# Emat_300v.net
KiCad netlist of a schematic drawn in EAGLE
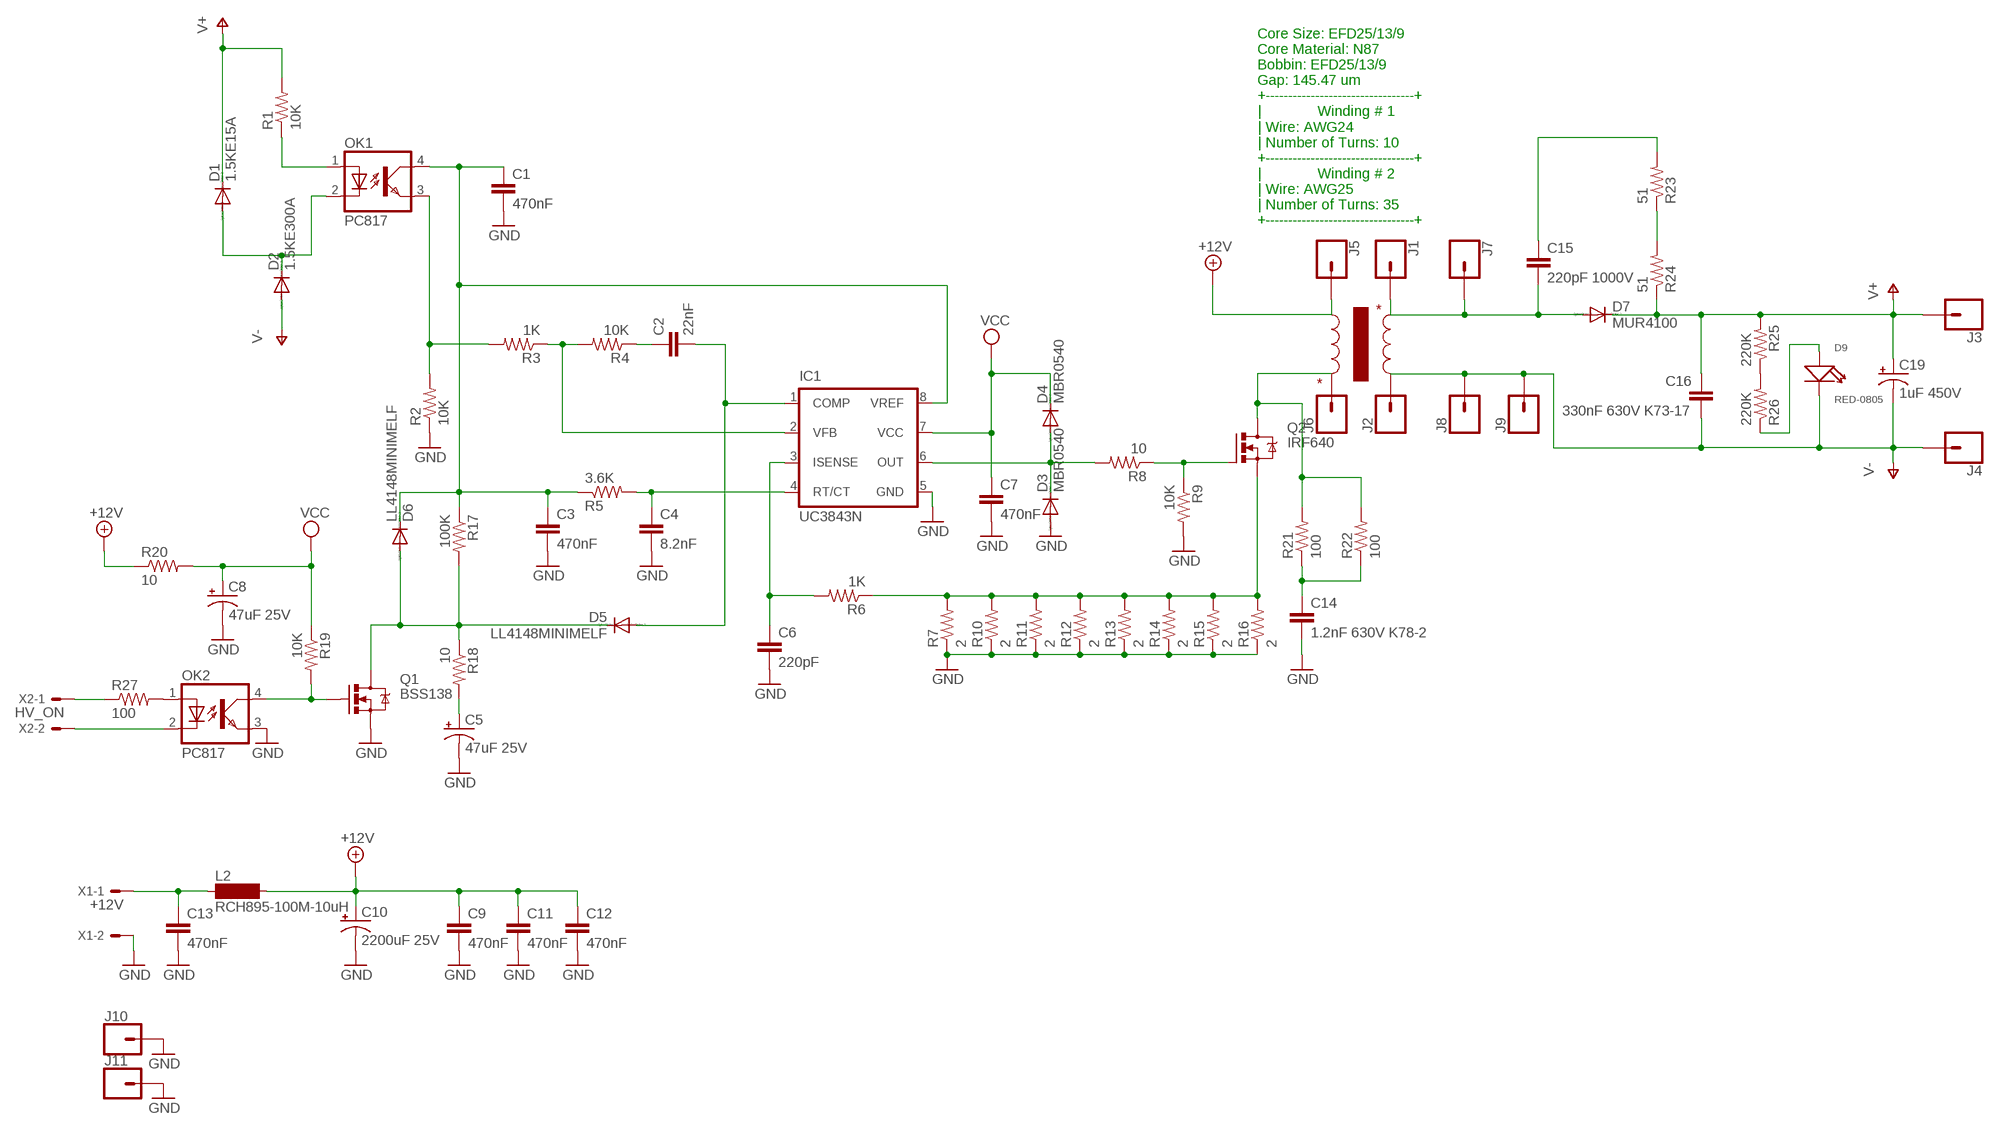
[diagram p0: schematic, sheet 1]

(export (version "E")
  (design (tool "Eeschema 10.0.6"))
  (components
    (comp (ref "C1")
      (value "470nF")
      (footprint "eagle-import:C0805")
      (libsource (lib "eagle-import") (part "C-EUC0805"))
    )
    (comp (ref "C2")
      (value "22nF")
      (footprint "eagle-import:C0805")
      (libsource (lib "eagle-import") (part "C-EUC0805"))
    )
    (comp (ref "C3")
      (value "470nF")
      (footprint "eagle-import:C0805")
      (libsource (lib "eagle-import") (part "C-EUC0805"))
    )
    (comp (ref "C4")
      (value "8.2nF")
      (footprint "eagle-import:C0805")
      (libsource (lib "eagle-import") (part "C-EUC0805"))
    )
    (comp (ref "C5")
      (value "47uF 25V")
      (footprint "eagle-import:E5-8,5")
      (libsource (lib "eagle-import") (part "CPOL-USE5-8.5"))
    )
    (comp (ref "C6")
      (value "220pF")
      (footprint "eagle-import:C0805")
      (libsource (lib "eagle-import") (part "C-EUC0805"))
    )
    (comp (ref "C7")
      (value "470nF")
      (footprint "eagle-import:C0805")
      (libsource (lib "eagle-import") (part "C-EUC0805"))
    )
    (comp (ref "C8")
      (value "47uF 25V")
      (footprint "eagle-import:E5-8,5")
      (libsource (lib "eagle-import") (part "CPOL-USE5-8.5"))
    )
    (comp (ref "C9")
      (value "470nF")
      (footprint "eagle-import:C0805")
      (libsource (lib "eagle-import") (part "C-EUC0805"))
    )
    (comp (ref "C10")
      (value "2200uF 25V")
      (footprint "eagle-import:E7,5-18")
      (libsource (lib "eagle-import") (part "CPOL-USE7.5-18"))
    )
    (comp (ref "C11")
      (value "470nF")
      (footprint "eagle-import:C0805")
      (libsource (lib "eagle-import") (part "C-EUC0805"))
    )
    (comp (ref "C12")
      (value "470nF")
      (footprint "eagle-import:C0805")
      (libsource (lib "eagle-import") (part "C-EUC0805"))
    )
    (comp (ref "C13")
      (value "470nF")
      (footprint "eagle-import:C0805")
      (libsource (lib "eagle-import") (part "C-EUC0805"))
    )
    (comp (ref "C14")
      (value "1.2nF 630V K78-2")
      (footprint "eagle-import:C150-064X183")
      (libsource (lib "eagle-import") (part "C-EU150-064X183"))
    )
    (comp (ref "C15")
      (value "220pF 1000V")
      (footprint "eagle-import:C075-042X103")
      (libsource (lib "eagle-import") (part "C-EU075-042X103"))
    )
    (comp (ref "C16")
      (value "330nF 630V K73-17")
      (footprint "eagle-import:C225-062X268")
      (libsource (lib "eagle-import") (part "C-EU225-062X268"))
    )
    (comp (ref "C19")
      (value "1uF 450V")
      (footprint "eagle-import:E5-8,5")
      (libsource (lib "eagle-import") (part "CPOL-USE5-8.5"))
    )
    (comp (ref "D1")
      (value "1.5KE15A")
      (footprint "eagle-import:DO201-15")
      (libsource (lib "eagle-import") (part "DIODE-DO201-15"))
    )
    (comp (ref "D2")
      (value "1.5KE300A")
      (footprint "eagle-import:DO201-15")
      (libsource (lib "eagle-import") (part "DIODE-DO201-15"))
    )
    (comp (ref "D3")
      (value "MBR0540")
      (footprint "eagle-import:SOD123")
      (libsource (lib "eagle-import") (part "DIODE-SOD123"))
    )
    (comp (ref "D4")
      (value "MBR0540")
      (footprint "eagle-import:SOD123")
      (libsource (lib "eagle-import") (part "DIODE-SOD123"))
    )
    (comp (ref "D5")
      (value "LL4148MINIMELF")
      (footprint "eagle-import:MINIMELF")
      (libsource (lib "eagle-import") (part "LL4148MINIMELF"))
    )
    (comp (ref "D6")
      (value "LL4148MINIMELF")
      (footprint "eagle-import:MINIMELF")
      (libsource (lib "eagle-import") (part "LL4148MINIMELF"))
    )
    (comp (ref "D7")
      (value "MUR4100")
      (footprint "eagle-import:DO201-15")
      (libsource (lib "eagle-import") (part "DIODE-DO201-15"))
    )
    (comp (ref "D9")
      (value "RED-0805")
      (footprint "eagle-import:LED-0805")
      (fields (field (name "MPN") "17-215SYGC/S530-E2/TR8"))
      (libsource (lib "eagle-import") (part "SMD-LED-CLEAR-GREEN(0805)"))
    )
    (comp (ref "IC1")
      (value "UC3843N")
      (footprint "eagle-import:DIL08")
      (libsource (lib "eagle-import") (part "UC384N3"))
    )
    (comp (ref "J1")
      (value "CONN_01PTH_NO_SILK_KIT")
      (footprint "eagle-import:1X01NS_KIT")
      (libsource (lib "eagle-import") (part "CONN_01PTH_NO_SILK_KIT"))
    )
    (comp (ref "J2")
      (value "CONN_01PTH_NO_SILK_KIT")
      (footprint "eagle-import:1X01NS_KIT")
      (libsource (lib "eagle-import") (part "CONN_01PTH_NO_SILK_KIT"))
    )
    (comp (ref "J3")
      (value "CONN_01PTH_NO_SILK_KIT")
      (footprint "eagle-import:1X01NS_KIT")
      (libsource (lib "eagle-import") (part "CONN_01PTH_NO_SILK_KIT"))
    )
    (comp (ref "J4")
      (value "CONN_01PTH_NO_SILK_KIT")
      (footprint "eagle-import:1X01NS_KIT")
      (libsource (lib "eagle-import") (part "CONN_01PTH_NO_SILK_KIT"))
    )
    (comp (ref "J5")
      (value "CONN_01PTH_NO_SILK_KIT")
      (footprint "eagle-import:1X01NS_KIT")
      (libsource (lib "eagle-import") (part "CONN_01PTH_NO_SILK_KIT"))
    )
    (comp (ref "J6")
      (value "CONN_01PTH_NO_SILK_KIT")
      (footprint "eagle-import:1X01NS_KIT")
      (libsource (lib "eagle-import") (part "CONN_01PTH_NO_SILK_KIT"))
    )
    (comp (ref "J7")
      (value "CONN_01PTH_NO_SILK_KIT")
      (footprint "eagle-import:1X01NS_KIT")
      (libsource (lib "eagle-import") (part "CONN_01PTH_NO_SILK_KIT"))
    )
    (comp (ref "J8")
      (value "CONN_01PTH_NO_SILK_KIT")
      (footprint "eagle-import:1X01NS_KIT")
      (libsource (lib "eagle-import") (part "CONN_01PTH_NO_SILK_KIT"))
    )
    (comp (ref "J9")
      (value "CONN_01PTH_NO_SILK_KIT")
      (footprint "eagle-import:1X01NS_KIT")
      (libsource (lib "eagle-import") (part "CONN_01PTH_NO_SILK_KIT"))
    )
    (comp (ref "J10")
      (value "CONN_01PTH_NO_SILK_KIT")
      (footprint "eagle-import:1X01NS_KIT")
      (libsource (lib "eagle-import") (part "CONN_01PTH_NO_SILK_KIT"))
    )
    (comp (ref "J11")
      (value "CONN_01PTH_NO_SILK_KIT")
      (footprint "eagle-import:1X01NS_KIT")
      (libsource (lib "eagle-import") (part "CONN_01PTH_NO_SILK_KIT"))
    )
    (comp (ref "L2")
      (value "RCH895-100M-10uH")
      (footprint "eagle-import:BS11")
      (libsource (lib "eagle-import") (part "RCH-89511"))
    )
    (comp (ref "OK1")
      (value "PC817")
      (footprint "eagle-import:DIL04")
      (fields (field (name "MPN") "PC817X4J000F"))
      (libsource (lib "eagle-import") (part "PC817"))
    )
    (comp (ref "OK2")
      (value "PC817")
      (footprint "eagle-import:DIL04")
      (fields (field (name "MPN") "PC817X4J000F"))
      (libsource (lib "eagle-import") (part "PC817"))
    )
    (comp (ref "Q1")
      (value "BSS138")
      (footprint "eagle-import:SOT23-3")
      (libsource (lib "eagle-import") (part "MOSFET-NCHANNELBSS138"))
    )
    (comp (ref "Q2")
      (value "IRF640")
      (footprint "eagle-import:TO220BV")
      (libsource (lib "eagle-import") (part "IRF640"))
    )
    (comp (ref "R1")
      (value "10K")
      (footprint "eagle-import:R1206")
      (libsource (lib "eagle-import") (part "R-US_R1206"))
    )
    (comp (ref "R2")
      (value "10K")
      (footprint "eagle-import:R1206")
      (libsource (lib "eagle-import") (part "R-US_R1206"))
    )
    (comp (ref "R3")
      (value "1K")
      (footprint "eagle-import:R1206")
      (libsource (lib "eagle-import") (part "R-US_R1206"))
    )
    (comp (ref "R4")
      (value "10K")
      (footprint "eagle-import:R1206")
      (libsource (lib "eagle-import") (part "R-US_R1206"))
    )
    (comp (ref "R5")
      (value "3.6K")
      (footprint "eagle-import:R1206")
      (libsource (lib "eagle-import") (part "R-US_R1206"))
    )
    (comp (ref "R6")
      (value "1K")
      (footprint "eagle-import:R1206")
      (libsource (lib "eagle-import") (part "R-US_R1206"))
    )
    (comp (ref "R7")
      (value "2")
      (footprint "eagle-import:R1206")
      (libsource (lib "eagle-import") (part "R-US_R1206"))
    )
    (comp (ref "R8")
      (value "10")
      (footprint "eagle-import:R1206")
      (libsource (lib "eagle-import") (part "R-US_R1206"))
    )
    (comp (ref "R9")
      (value "10K")
      (footprint "eagle-import:R1206")
      (libsource (lib "eagle-import") (part "R-US_R1206"))
    )
    (comp (ref "R10")
      (value "2")
      (footprint "eagle-import:R1206")
      (libsource (lib "eagle-import") (part "R-US_R1206"))
    )
    (comp (ref "R11")
      (value "2")
      (footprint "eagle-import:R1206")
      (libsource (lib "eagle-import") (part "R-US_R1206"))
    )
    (comp (ref "R12")
      (value "2")
      (footprint "eagle-import:R1206")
      (libsource (lib "eagle-import") (part "R-US_R1206"))
    )
    (comp (ref "R13")
      (value "2")
      (footprint "eagle-import:R1206")
      (libsource (lib "eagle-import") (part "R-US_R1206"))
    )
    (comp (ref "R14")
      (value "2")
      (footprint "eagle-import:R1206")
      (libsource (lib "eagle-import") (part "R-US_R1206"))
    )
    (comp (ref "R15")
      (value "2")
      (footprint "eagle-import:R1206")
      (libsource (lib "eagle-import") (part "R-US_R1206"))
    )
    (comp (ref "R16")
      (value "2")
      (footprint "eagle-import:R1206")
      (libsource (lib "eagle-import") (part "R-US_R1206"))
    )
    (comp (ref "R17")
      (value "100K")
      (footprint "eagle-import:R1206")
      (libsource (lib "eagle-import") (part "R-US_R1206"))
    )
    (comp (ref "R18")
      (value "10")
      (footprint "eagle-import:R1206")
      (libsource (lib "eagle-import") (part "R-US_R1206"))
    )
    (comp (ref "R19")
      (value "10K")
      (footprint "eagle-import:R1206")
      (libsource (lib "eagle-import") (part "R-US_R1206"))
    )
    (comp (ref "R20")
      (value "10")
      (footprint "eagle-import:R1206")
      (libsource (lib "eagle-import") (part "R-US_R1206"))
    )
    (comp (ref "R21")
      (value "100")
      (footprint "eagle-import:R2512")
      (libsource (lib "eagle-import") (part "R-US_R2512"))
    )
    (comp (ref "R22")
      (value "100")
      (footprint "eagle-import:R2512")
      (libsource (lib "eagle-import") (part "R-US_R2512"))
    )
    (comp (ref "R23")
      (value "51")
      (footprint "eagle-import:R1206")
      (libsource (lib "eagle-import") (part "R-US_R1206"))
    )
    (comp (ref "R24")
      (value "51")
      (footprint "eagle-import:R1206")
      (libsource (lib "eagle-import") (part "R-US_R1206"))
    )
    (comp (ref "R25")
      (value "220K")
      (footprint "eagle-import:R1206")
      (libsource (lib "eagle-import") (part "R-US_R1206"))
    )
    (comp (ref "R26")
      (value "220K")
      (footprint "eagle-import:R1206")
      (libsource (lib "eagle-import") (part "R-US_R1206"))
    )
    (comp (ref "R27")
      (value "100")
      (footprint "eagle-import:R1206")
      (libsource (lib "eagle-import") (part "R-US_R1206"))
    )
    (comp (ref "X1")
      (value "+12V")
      (footprint "eagle-import:22-23-2021")
      (fields (field (name "MF") "MOLEX") (field (name "MPN") "22-23-2021"))
      (libsource (lib "eagle-import") (part "22-23-2021"))
    )
    (comp (ref "X2")
      (value "HV_ON")
      (footprint "eagle-import:22-23-2021")
      (fields (field (name "MF") "MOLEX") (field (name "MPN") "22-23-2021"))
      (libsource (lib "eagle-import") (part "22-23-2021"))
    )
  )
  (nets
    (net (code "1") (name "+12V") (class "Default")
      (node (ref "C10") (pin "+") (pinfunction "+_+") (pintype "passive"))
      (node (ref "C11") (pin "1") (pinfunction "1_1") (pintype "passive"))
      (node (ref "C12") (pin "1") (pinfunction "1_1") (pintype "passive"))
      (node (ref "C9") (pin "1") (pinfunction "1_1") (pintype "passive"))
      (node (ref "J5") (pin "1") (pinfunction "1_1") (pintype "passive"))
      (node (ref "L2") (pin "2") (pinfunction "2_2") (pintype "passive"))
      (node (ref "R20") (pin "1") (pinfunction "1_1") (pintype "passive"))
    )
    (net (code "2") (name "GND") (class "Default")
      (node (ref "C1") (pin "2") (pinfunction "2_2") (pintype "passive"))
      (node (ref "C10") (pin "-") (pinfunction "-_-") (pintype "passive"))
      (node (ref "C11") (pin "2") (pinfunction "2_2") (pintype "passive"))
      (node (ref "C12") (pin "2") (pinfunction "2_2") (pintype "passive"))
      (node (ref "C13") (pin "2") (pinfunction "2_2") (pintype "passive"))
      (node (ref "C14") (pin "2") (pinfunction "2_2") (pintype "passive"))
      (node (ref "C3") (pin "2") (pinfunction "2_2") (pintype "passive"))
      (node (ref "C4") (pin "2") (pinfunction "2_2") (pintype "passive"))
      (node (ref "C5") (pin "-") (pinfunction "-_-") (pintype "passive"))
      (node (ref "C6") (pin "2") (pinfunction "2_2") (pintype "passive"))
      (node (ref "C7") (pin "2") (pinfunction "2_2") (pintype "passive"))
      (node (ref "C8") (pin "-") (pinfunction "-_-") (pintype "passive"))
      (node (ref "C9") (pin "2") (pinfunction "2_2") (pintype "passive"))
      (node (ref "D3") (pin "A") (pinfunction "A_A") (pintype "passive"))
      (node (ref "IC1") (pin "5") (pinfunction "GND_5") (pintype "power_in"))
      (node (ref "J10") (pin "1") (pinfunction "1_1") (pintype "passive"))
      (node (ref "J11") (pin "1") (pinfunction "1_1") (pintype "passive"))
      (node (ref "OK2") (pin "3") (pinfunction "EMIT_3") (pintype "passive"))
      (node (ref "Q1") (pin "2") (pinfunction "S_2") (pintype "passive"))
      (node (ref "R10") (pin "1") (pinfunction "1_1") (pintype "passive"))
      (node (ref "R11") (pin "1") (pinfunction "1_1") (pintype "passive"))
      (node (ref "R12") (pin "1") (pinfunction "1_1") (pintype "passive"))
      (node (ref "R13") (pin "1") (pinfunction "1_1") (pintype "passive"))
      (node (ref "R14") (pin "1") (pinfunction "1_1") (pintype "passive"))
      (node (ref "R15") (pin "1") (pinfunction "1_1") (pintype "passive"))
      (node (ref "R16") (pin "1") (pinfunction "1_1") (pintype "passive"))
      (node (ref "R2") (pin "1") (pinfunction "1_1") (pintype "passive"))
      (node (ref "R7") (pin "1") (pinfunction "1_1") (pintype "passive"))
      (node (ref "R9") (pin "2") (pinfunction "2_2") (pintype "passive"))
      (node (ref "X1") (pin "2") (pinfunction "S_2") (pintype "passive"))
    )
    (net (code "3") (name "Net-(C2-Pad1)") (class "Default")
      (node (ref "C2") (pin "1") (pinfunction "1_1") (pintype "passive"))
      (node (ref "R4") (pin "1") (pinfunction "1_1") (pintype "passive"))
    )
    (net (code "4") (name "Net-(C5-Pad+)") (class "Default")
      (node (ref "C5") (pin "+") (pinfunction "+_+") (pintype "passive"))
      (node (ref "R18") (pin "2") (pinfunction "2_2") (pintype "passive"))
    )
    (net (code "5") (name "Net-(C14-Pad1)") (class "Default")
      (node (ref "C14") (pin "1") (pinfunction "1_1") (pintype "passive"))
      (node (ref "R21") (pin "1") (pinfunction "1_1") (pintype "passive"))
      (node (ref "R22") (pin "1") (pinfunction "1_1") (pintype "passive"))
    )
    (net (code "6") (name "Net-(C15-Pad1)") (class "Default")
      (node (ref "C15") (pin "1") (pinfunction "1_1") (pintype "passive"))
      (node (ref "R23") (pin "2") (pinfunction "2_2") (pintype "passive"))
    )
    (net (code "7") (name "Net-(C15-Pad2)") (class "Default")
      (node (ref "C15") (pin "2") (pinfunction "2_2") (pintype "passive"))
      (node (ref "D7") (pin "A") (pinfunction "A_A") (pintype "passive"))
      (node (ref "J1") (pin "1") (pinfunction "1_1") (pintype "passive"))
      (node (ref "J7") (pin "1") (pinfunction "1_1") (pintype "passive"))
    )
    (net (code "8") (name "Net-(D9-Pad+)") (class "Default")
      (node (ref "D9") (pin "+") (pinfunction "+_+") (pintype "passive"))
      (node (ref "R26") (pin "1") (pinfunction "1_1") (pintype "passive"))
    )
    (net (code "9") (name "Net-(IC1-COMP)") (class "Default")
      (node (ref "C2") (pin "2") (pinfunction "2_2") (pintype "passive"))
      (node (ref "D5") (pin "A") (pinfunction "A_A") (pintype "passive"))
      (node (ref "IC1") (pin "1") (pinfunction "COMP_1") (pintype "passive"))
    )
    (net (code "10") (name "Net-(IC1-ISENSE)") (class "Default")
      (node (ref "C6") (pin "1") (pinfunction "1_1") (pintype "passive"))
      (node (ref "IC1") (pin "3") (pinfunction "ISENSE_3") (pintype "input"))
      (node (ref "R6") (pin "2") (pinfunction "2_2") (pintype "passive"))
    )
    (net (code "11") (name "Net-(IC1-OUT)") (class "Default")
      (node (ref "D3") (pin "C") (pinfunction "C_C") (pintype "passive"))
      (node (ref "D4") (pin "A") (pinfunction "A_A") (pintype "passive"))
      (node (ref "IC1") (pin "6") (pinfunction "OUT_6") (pintype "output"))
      (node (ref "R8") (pin "2") (pinfunction "2_2") (pintype "passive"))
    )
    (net (code "12") (name "Net-(IC1-RT{slash}CT)") (class "Default")
      (node (ref "C4") (pin "1") (pinfunction "1_1") (pintype "passive"))
      (node (ref "IC1") (pin "4") (pinfunction "RT/CT_4") (pintype "passive"))
      (node (ref "R5") (pin "2") (pinfunction "2_2") (pintype "passive"))
    )
    (net (code "13") (name "Net-(IC1-VFB)") (class "Default")
      (node (ref "IC1") (pin "2") (pinfunction "VFB_2") (pintype "input"))
      (node (ref "R3") (pin "1") (pinfunction "1_1") (pintype "passive"))
      (node (ref "R4") (pin "2") (pinfunction "2_2") (pintype "passive"))
    )
    (net (code "14") (name "Net-(IC1-VREF)") (class "Default")
      (node (ref "C1") (pin "1") (pinfunction "1_1") (pintype "passive"))
      (node (ref "C3") (pin "1") (pinfunction "1_1") (pintype "passive"))
      (node (ref "D6") (pin "C") (pinfunction "C_C") (pintype "passive"))
      (node (ref "IC1") (pin "8") (pinfunction "VREF_8") (pintype "passive"))
      (node (ref "OK1") (pin "4") (pinfunction "COL_4") (pintype "passive"))
      (node (ref "R17") (pin "1") (pinfunction "1_1") (pintype "passive"))
      (node (ref "R5") (pin "1") (pinfunction "1_1") (pintype "passive"))
    )
    (net (code "15") (name "Net-(J6-Pad1)") (class "Default")
      (node (ref "J6") (pin "1") (pinfunction "1_1") (pintype "passive"))
      (node (ref "Q2") (pin "D") (pinfunction "D_D") (pintype "passive"))
      (node (ref "R21") (pin "2") (pinfunction "2_2") (pintype "passive"))
      (node (ref "R22") (pin "2") (pinfunction "2_2") (pintype "passive"))
    )
    (net (code "16") (name "Net-(OK1-A)") (class "Default")
      (node (ref "OK1") (pin "1") (pinfunction "A_1") (pintype "passive"))
      (node (ref "R1") (pin "1") (pinfunction "1_1") (pintype "passive"))
    )
    (net (code "17") (name "Net-(OK1-C)") (class "Default")
      (node (ref "D1") (pin "A") (pinfunction "A_A") (pintype "passive"))
      (node (ref "D2") (pin "C") (pinfunction "C_C") (pintype "passive"))
      (node (ref "OK1") (pin "2") (pinfunction "C_2") (pintype "passive"))
    )
    (net (code "18") (name "Net-(OK1-EMIT)") (class "Default")
      (node (ref "OK1") (pin "3") (pinfunction "EMIT_3") (pintype "passive"))
      (node (ref "R2") (pin "2") (pinfunction "2_2") (pintype "passive"))
      (node (ref "R3") (pin "2") (pinfunction "2_2") (pintype "passive"))
    )
    (net (code "19") (name "Net-(OK2-A)") (class "Default")
      (node (ref "OK2") (pin "1") (pinfunction "A_1") (pintype "passive"))
      (node (ref "R27") (pin "2") (pinfunction "2_2") (pintype "passive"))
    )
    (net (code "20") (name "Net-(OK2-C)") (class "Default")
      (node (ref "OK2") (pin "2") (pinfunction "C_2") (pintype "passive"))
      (node (ref "X2") (pin "2") (pinfunction "S_2") (pintype "passive"))
    )
    (net (code "21") (name "Net-(OK2-COL)") (class "Default")
      (node (ref "OK2") (pin "4") (pinfunction "COL_4") (pintype "passive"))
      (node (ref "Q1") (pin "1") (pinfunction "G_1") (pintype "passive"))
      (node (ref "R19") (pin "2") (pinfunction "2_2") (pintype "passive"))
    )
    (net (code "22") (name "Net-(Q1-D)") (class "Default")
      (node (ref "D5") (pin "C") (pinfunction "C_C") (pintype "passive"))
      (node (ref "D6") (pin "A") (pinfunction "A_A") (pintype "passive"))
      (node (ref "Q1") (pin "3") (pinfunction "D_3") (pintype "passive"))
      (node (ref "R17") (pin "2") (pinfunction "2_2") (pintype "passive"))
      (node (ref "R18") (pin "1") (pinfunction "1_1") (pintype "passive"))
    )
    (net (code "23") (name "Net-(Q2-PadG)") (class "Default")
      (node (ref "Q2") (pin "G") (pinfunction "G_G") (pintype "passive"))
      (node (ref "R8") (pin "1") (pinfunction "1_1") (pintype "passive"))
      (node (ref "R9") (pin "1") (pinfunction "1_1") (pintype "passive"))
    )
    (net (code "24") (name "Net-(Q2-PadS)") (class "Default")
      (node (ref "Q2") (pin "S") (pinfunction "S_S") (pintype "passive"))
      (node (ref "R10") (pin "2") (pinfunction "2_2") (pintype "passive"))
      (node (ref "R11") (pin "2") (pinfunction "2_2") (pintype "passive"))
      (node (ref "R12") (pin "2") (pinfunction "2_2") (pintype "passive"))
      (node (ref "R13") (pin "2") (pinfunction "2_2") (pintype "passive"))
      (node (ref "R14") (pin "2") (pinfunction "2_2") (pintype "passive"))
      (node (ref "R15") (pin "2") (pinfunction "2_2") (pintype "passive"))
      (node (ref "R16") (pin "2") (pinfunction "2_2") (pintype "passive"))
      (node (ref "R6") (pin "1") (pinfunction "1_1") (pintype "passive"))
      (node (ref "R7") (pin "2") (pinfunction "2_2") (pintype "passive"))
    )
    (net (code "25") (name "Net-(R23-Pad1)") (class "Default")
      (node (ref "R23") (pin "1") (pinfunction "1_1") (pintype "passive"))
      (node (ref "R24") (pin "2") (pinfunction "2_2") (pintype "passive"))
    )
    (net (code "26") (name "Net-(R25-Pad1)") (class "Default")
      (node (ref "R25") (pin "1") (pinfunction "1_1") (pintype "passive"))
      (node (ref "R26") (pin "2") (pinfunction "2_2") (pintype "passive"))
    )
    (net (code "27") (name "Net-(X1A-S)") (class "Default")
      (node (ref "C13") (pin "1") (pinfunction "1_1") (pintype "passive"))
      (node (ref "L2") (pin "1") (pinfunction "1_1") (pintype "passive"))
      (node (ref "X1") (pin "1") (pinfunction "S_1") (pintype "passive"))
    )
    (net (code "28") (name "Net-(X2A-S)") (class "Default")
      (node (ref "R27") (pin "1") (pinfunction "1_1") (pintype "passive"))
      (node (ref "X2") (pin "1") (pinfunction "S_1") (pintype "passive"))
    )
    (net (code "29") (name "V+") (class "Default")
      (node (ref "C16") (pin "1") (pinfunction "1_1") (pintype "passive"))
      (node (ref "C19") (pin "+") (pinfunction "+_+") (pintype "passive"))
      (node (ref "D1") (pin "C") (pinfunction "C_C") (pintype "passive"))
      (node (ref "D7") (pin "C") (pinfunction "C_C") (pintype "passive"))
      (node (ref "J3") (pin "1") (pinfunction "1_1") (pintype "passive"))
      (node (ref "R1") (pin "2") (pinfunction "2_2") (pintype "passive"))
      (node (ref "R24") (pin "1") (pinfunction "1_1") (pintype "passive"))
      (node (ref "R25") (pin "2") (pinfunction "2_2") (pintype "passive"))
    )
    (net (code "30") (name "V-") (class "Default")
      (node (ref "C16") (pin "2") (pinfunction "2_2") (pintype "passive"))
      (node (ref "C19") (pin "-") (pinfunction "-_-") (pintype "passive"))
      (node (ref "D2") (pin "A") (pinfunction "A_A") (pintype "passive"))
      (node (ref "D9") (pin "-") (pinfunction "-_-") (pintype "passive"))
      (node (ref "J2") (pin "1") (pinfunction "1_1") (pintype "passive"))
      (node (ref "J4") (pin "1") (pinfunction "1_1") (pintype "passive"))
      (node (ref "J8") (pin "1") (pinfunction "1_1") (pintype "passive"))
      (node (ref "J9") (pin "1") (pinfunction "1_1") (pintype "passive"))
    )
    (net (code "31") (name "VCC") (class "Default")
      (node (ref "C7") (pin "1") (pinfunction "1_1") (pintype "passive"))
      (node (ref "C8") (pin "+") (pinfunction "+_+") (pintype "passive"))
      (node (ref "D4") (pin "C") (pinfunction "C_C") (pintype "passive"))
      (node (ref "IC1") (pin "7") (pinfunction "VCC_7") (pintype "power_in"))
      (node (ref "R19") (pin "1") (pinfunction "1_1") (pintype "passive"))
      (node (ref "R20") (pin "2") (pinfunction "2_2") (pintype "passive"))
    )
  )
)
